# SparkFun_tDof-TMF8821_Mini.net
KiCad netlist of a schematic drawn in EAGLE
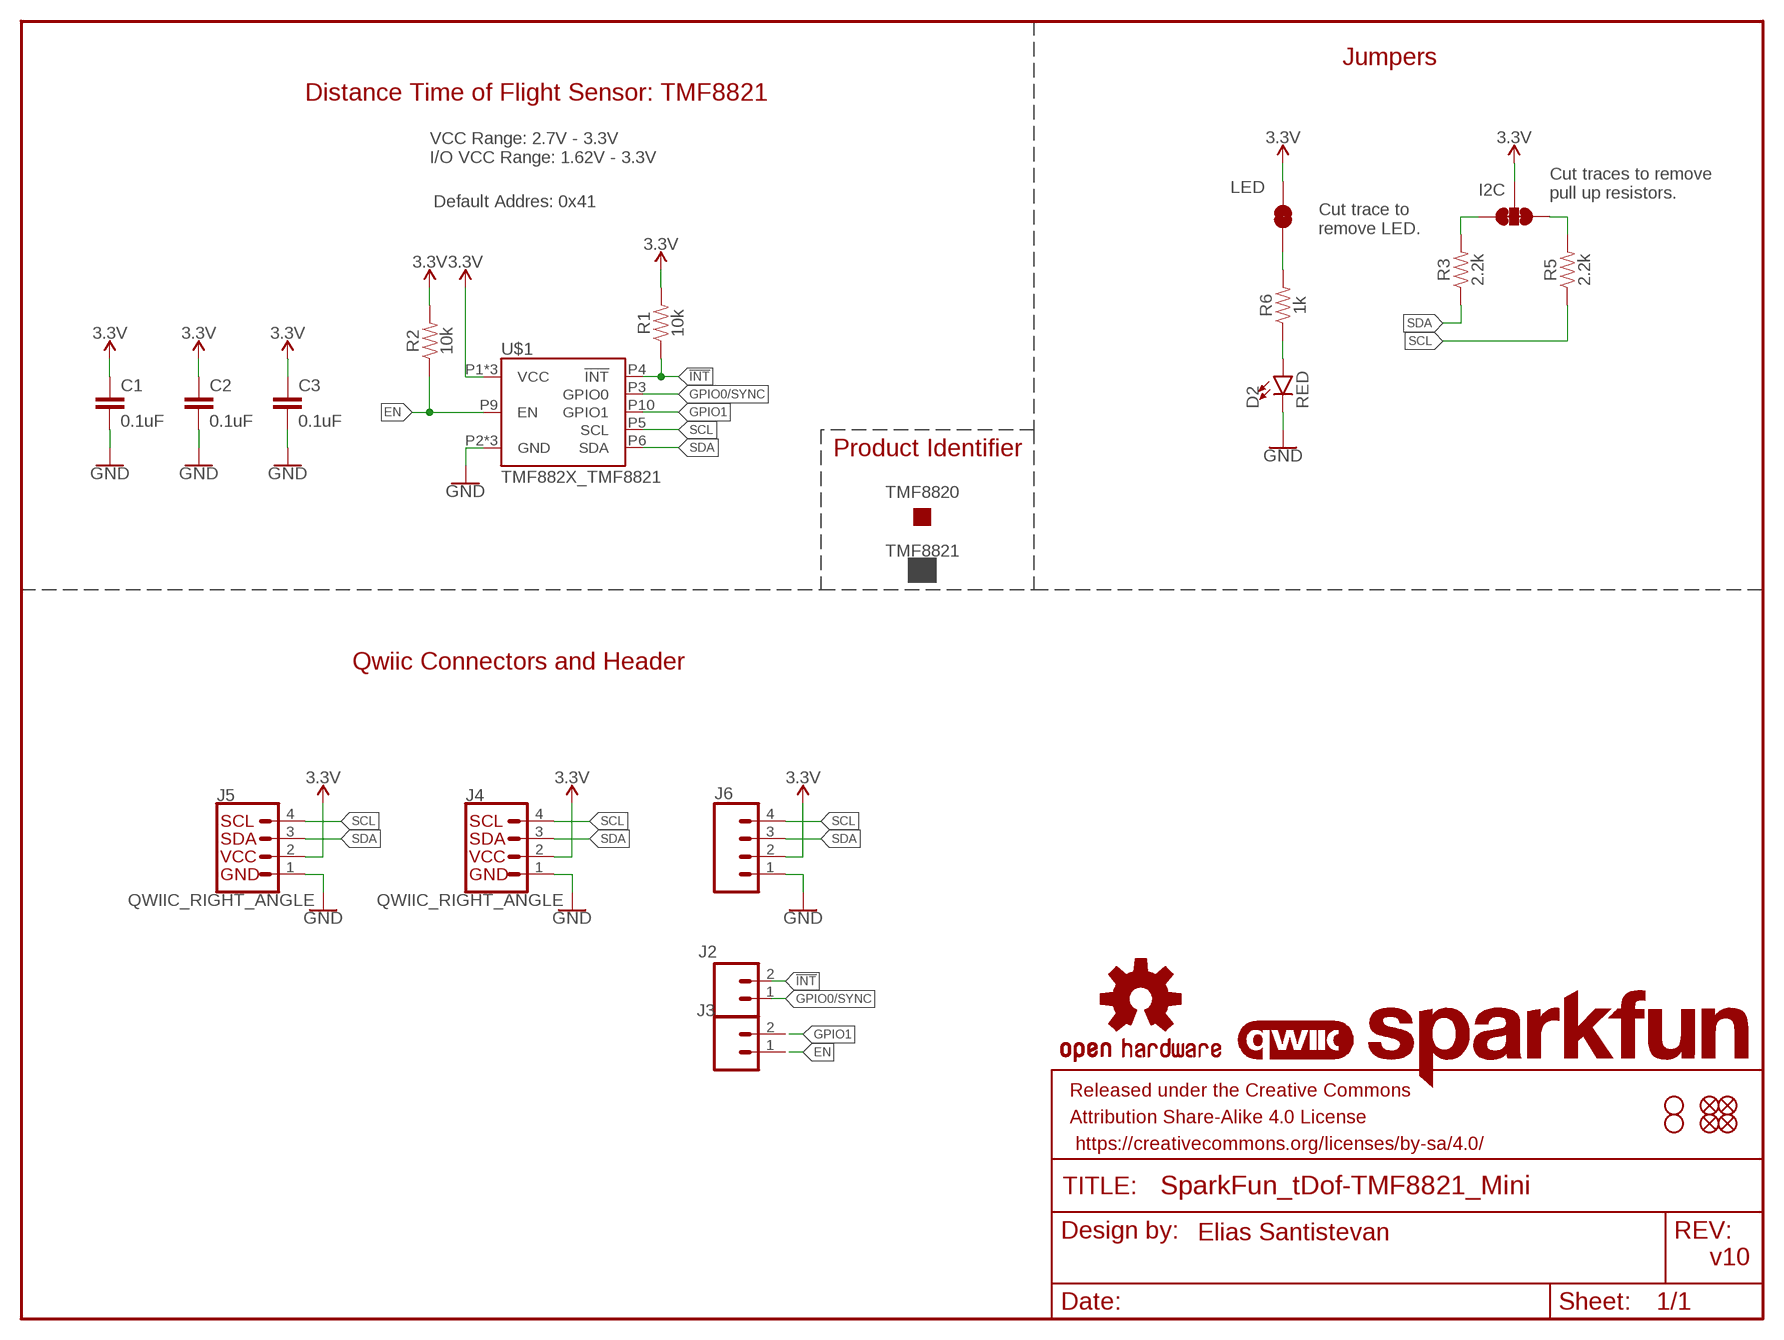
[diagram p0: schematic, sheet 1]

(export (version "E")
  (design (tool "Eeschema 10.0.6"))
  (components
    (comp (ref "C1")
      (value "0.1uF")
      (footprint "eagle-import:0402-TIGHT")
      (libsource (lib "eagle-import") (part "0.1UF-0402T-6.3V-10%-X7R"))
    )
    (comp (ref "C2")
      (value "0.1uF")
      (footprint "eagle-import:0402-TIGHT")
      (libsource (lib "eagle-import") (part "0.1UF-0402T-6.3V-10%-X7R"))
    )
    (comp (ref "C3")
      (value "0.1uF")
      (footprint "eagle-import:0402-TIGHT")
      (libsource (lib "eagle-import") (part "0.1UF-0402T-6.3V-10%-X7R"))
    )
    (comp (ref "D2")
      (value "RED")
      (footprint "eagle-import:LED-0603")
      (libsource (lib "eagle-import") (part "LED-RED0603"))
    )
    (comp (ref "FD5")
      (value "FIDUCIALUFIDUCIAL")
      (footprint "eagle-import:FIDUCIAL-MICRO")
      (libsource (lib "eagle-import") (part "FIDUCIALUFIDUCIAL"))
    )
    (comp (ref "FD6")
      (value "FIDUCIALUFIDUCIAL")
      (footprint "eagle-import:FIDUCIAL-MICRO")
      (libsource (lib "eagle-import") (part "FIDUCIALUFIDUCIAL"))
    )
    (comp (ref "FD7")
      (value "FIDUCIALUFIDUCIAL")
      (footprint "eagle-import:FIDUCIAL-MICRO")
      (libsource (lib "eagle-import") (part "FIDUCIALUFIDUCIAL"))
    )
    (comp (ref "FD8")
      (value "FIDUCIALUFIDUCIAL")
      (footprint "eagle-import:FIDUCIAL-MICRO")
      (libsource (lib "eagle-import") (part "FIDUCIALUFIDUCIAL"))
    )
    (comp (ref "FRAME2")
      (value "FRAME-LETTER")
      (footprint "eagle-import:CREATIVE_COMMONS")
      (libsource (lib "eagle-import") (part "FRAME-LETTER"))
    )
    (comp (ref "H7")
      (value "STAND-OFFTIGHT")
      (footprint "eagle-import:STAND-OFF-TIGHT")
      (libsource (lib "eagle-import") (part "STAND-OFFTIGHT"))
    )
    (comp (ref "H8")
      (value "STAND-OFFTIGHT")
      (footprint "eagle-import:STAND-OFF-TIGHT")
      (libsource (lib "eagle-import") (part "STAND-OFFTIGHT"))
    )
    (comp (ref "I2C")
      (value "I2C_PU")
      (footprint "eagle-import:SMT-JUMPER_3_2-NC_TRACE_SILK")
      (libsource (lib "eagle-import") (part "JUMPER-SMT_3_2-NC_TRACE_SILK"))
    )
    (comp (ref "J2")
      (value "CONN_021X02_NO_SILK")
      (footprint "eagle-import:1X02_NO_SILK")
      (libsource (lib "eagle-import") (part "CONN_021X02_NO_SILK"))
    )
    (comp (ref "J3")
      (value "CONN_021X02_NO_SILK")
      (footprint "eagle-import:1X02_NO_SILK")
      (libsource (lib "eagle-import") (part "CONN_021X02_NO_SILK"))
    )
    (comp (ref "J4")
      (value "QWIIC_RIGHT_ANGLE")
      (footprint "eagle-import:JST04_1MM_RA")
      (libsource (lib "eagle-import") (part "QWIIC_CONNECTORJS-1MM"))
    )
    (comp (ref "J5")
      (value "QWIIC_RIGHT_ANGLE")
      (footprint "eagle-import:JST04_1MM_RA")
      (libsource (lib "eagle-import") (part "QWIIC_CONNECTORJS-1MM"))
    )
    (comp (ref "J6")
      (value "CONN_041X04_NO_SILK")
      (footprint "eagle-import:1X04_NO_SILK")
      (libsource (lib "eagle-import") (part "CONN_041X04_NO_SILK"))
    )
    (comp (ref "LED")
      (value "LED")
      (footprint "eagle-import:SMT-JUMPER_2_NC_TRACE_SILK")
      (libsource (lib "eagle-import") (part "JUMPER-SMT_2_NC_TRACE_SILK"))
    )
    (comp (ref "LOGO1")
      (value "SFE_LOGO_NAMEBLANK")
      (footprint "eagle-import:BLANK")
      (libsource (lib "eagle-import") (part "SFE_LOGO_NAMEBLANK"))
    )
    (comp (ref "LOGO2")
      (value "QWIIC_LOGO_4MM")
      (footprint "eagle-import:QWIIC_4MM")
      (libsource (lib "eagle-import") (part "QWIIC_LOGO_4MM"))
    )
    (comp (ref "LOGO3")
      (value "OSHW-LOGONO_SILK")
      (footprint "eagle-import:DUMMY")
      (libsource (lib "eagle-import") (part "OSHW-LOGONO_SILK"))
    )
    (comp (ref "R1")
      (value "10k")
      (footprint "eagle-import:0402-TIGHT")
      (libsource (lib "eagle-import") (part "10KOHM-0402T-1/16W-1%"))
    )
    (comp (ref "R2")
      (value "10k")
      (footprint "eagle-import:0402-TIGHT")
      (libsource (lib "eagle-import") (part "10KOHM-0402T-1/16W-1%"))
    )
    (comp (ref "R3")
      (value "2.2k")
      (footprint "eagle-import:0402-TIGHT")
      (libsource (lib "eagle-import") (part "2.2KOHM-0402T-1/16W-1%"))
    )
    (comp (ref "R5")
      (value "2.2k")
      (footprint "eagle-import:0402-TIGHT")
      (libsource (lib "eagle-import") (part "2.2KOHM-0402T-1/16W-1%"))
    )
    (comp (ref "R6")
      (value "1k")
      (footprint "eagle-import:0402-TIGHT")
      (libsource (lib "eagle-import") (part "1KOHM-0402T-1/16W-1%"))
    )
    (comp (ref "TMF8820")
      (value "PROD_ID_NO-PASTE_SILK")
      (footprint "eagle-import:PRODUCT_IDENT_NO_SILK")
      (libsource (lib "eagle-import") (part "PROD_ID_NO-PASTE_SILK"))
    )
    (comp (ref "TMF8821")
      (value "PROD_ID_PASTE_SILK")
      (footprint "eagle-import:PRODUCT_IDENT_PASTE_SILK")
      (libsource (lib "eagle-import") (part "PROD_ID_PASTE_SILK"))
    )
    (comp (ref "U$1")
      (value "TMF882X_TMF8821")
      (footprint "eagle-import:TMF882X")
      (libsource (lib "eagle-import") (part "TMF882X_TMF8821"))
    )
  )
  (nets
    (net (code "1") (name "/~{INT}") (class "Default")
      (node (ref "J2") (pin "2") (pinfunction "2_2") (pintype "passive"))
      (node (ref "R1") (pin "1") (pinfunction "1_1") (pintype "passive"))
      (node (ref "U$1") (pin "P4") (pinfunction "~{INT}_P4") (pintype "bidirectional"))
    )
    (net (code "2") (name "3.3V") (class "Default")
      (node (ref "C1") (pin "1") (pinfunction "1_1") (pintype "passive"))
      (node (ref "C2") (pin "1") (pinfunction "1_1") (pintype "passive"))
      (node (ref "C3") (pin "1") (pinfunction "1_1") (pintype "passive"))
      (node (ref "I2C") (pin "2") (pinfunction "2_2") (pintype "passive"))
      (node (ref "J4") (pin "2") (pinfunction "2_2") (pintype "power_in"))
      (node (ref "J5") (pin "2") (pinfunction "2_2") (pintype "power_in"))
      (node (ref "J6") (pin "2") (pinfunction "2_2") (pintype "passive"))
      (node (ref "LED") (pin "2") (pinfunction "2_2") (pintype "passive"))
      (node (ref "R1") (pin "2") (pinfunction "2_2") (pintype "passive"))
      (node (ref "R2") (pin "2") (pinfunction "2_2") (pintype "passive"))
      (node (ref "U$1") (pin "P1") (pinfunction "VCC_P1") (pintype "power_in"))
      (node (ref "U$1") (pin "P12") (pinfunction "VCC_P12") (pintype "power_in"))
      (node (ref "U$1") (pin "P7") (pinfunction "VCC_P7") (pintype "power_in"))
    )
    (net (code "3") (name "EN") (class "Default")
      (node (ref "J3") (pin "1") (pinfunction "1_1") (pintype "passive"))
      (node (ref "R2") (pin "1") (pinfunction "1_1") (pintype "passive"))
      (node (ref "U$1") (pin "P9") (pinfunction "EN_P9") (pintype "input"))
    )
    (net (code "4") (name "GND") (class "Default")
      (node (ref "C1") (pin "2") (pinfunction "2_2") (pintype "passive"))
      (node (ref "C2") (pin "2") (pinfunction "2_2") (pintype "passive"))
      (node (ref "C3") (pin "2") (pinfunction "2_2") (pintype "passive"))
      (node (ref "D2") (pin "C") (pinfunction "C_C") (pintype "passive"))
      (node (ref "J4") (pin "1") (pinfunction "1_1") (pintype "power_in"))
      (node (ref "J5") (pin "1") (pinfunction "1_1") (pintype "power_in"))
      (node (ref "J6") (pin "1") (pinfunction "1_1") (pintype "passive"))
      (node (ref "U$1") (pin "P11") (pinfunction "GND_P11") (pintype "power_in"))
      (node (ref "U$1") (pin "P2") (pinfunction "GND_P2") (pintype "power_in"))
      (node (ref "U$1") (pin "P8") (pinfunction "GND_P8") (pintype "power_in"))
    )
    (net (code "5") (name "GPIO0{slash}SYNC") (class "Default")
      (node (ref "J2") (pin "1") (pinfunction "1_1") (pintype "passive"))
      (node (ref "U$1") (pin "P3") (pinfunction "GPIO0_P3") (pintype "bidirectional"))
    )
    (net (code "6") (name "GPIO1") (class "Default")
      (node (ref "J3") (pin "2") (pinfunction "2_2") (pintype "passive"))
      (node (ref "U$1") (pin "P10") (pinfunction "GPIO1_P10") (pintype "bidirectional"))
    )
    (net (code "7") (name "Net-(D2-PadA)") (class "Default")
      (node (ref "D2") (pin "A") (pinfunction "A_A") (pintype "passive"))
      (node (ref "R6") (pin "1") (pinfunction "1_1") (pintype "passive"))
    )
    (net (code "8") (name "Net-(I2C-Pad1)") (class "Default")
      (node (ref "I2C") (pin "1") (pinfunction "1_1") (pintype "passive"))
      (node (ref "R5") (pin "2") (pinfunction "2_2") (pintype "passive"))
    )
    (net (code "9") (name "Net-(I2C-Pad3)") (class "Default")
      (node (ref "I2C") (pin "3") (pinfunction "3_3") (pintype "passive"))
      (node (ref "R3") (pin "2") (pinfunction "2_2") (pintype "passive"))
    )
    (net (code "10") (name "Net-(LED-Pad1)") (class "Default")
      (node (ref "LED") (pin "1") (pinfunction "1_1") (pintype "passive"))
      (node (ref "R6") (pin "2") (pinfunction "2_2") (pintype "passive"))
    )
    (net (code "11") (name "SCL") (class "Default")
      (node (ref "J4") (pin "4") (pinfunction "4_4") (pintype "passive"))
      (node (ref "J5") (pin "4") (pinfunction "4_4") (pintype "passive"))
      (node (ref "J6") (pin "4") (pinfunction "4_4") (pintype "passive"))
      (node (ref "R5") (pin "1") (pinfunction "1_1") (pintype "passive"))
      (node (ref "U$1") (pin "P5") (pinfunction "SCL_P5") (pintype "bidirectional"))
    )
    (net (code "12") (name "SDA") (class "Default")
      (node (ref "J4") (pin "3") (pinfunction "3_3") (pintype "passive"))
      (node (ref "J5") (pin "3") (pinfunction "3_3") (pintype "passive"))
      (node (ref "J6") (pin "3") (pinfunction "3_3") (pintype "passive"))
      (node (ref "R3") (pin "1") (pinfunction "1_1") (pintype "passive"))
      (node (ref "U$1") (pin "P6") (pinfunction "SDA_P6") (pintype "bidirectional"))
    )
  )
)
